# HeatBedRelay5d.net
KiCad netlist of a schematic drawn in EAGLE
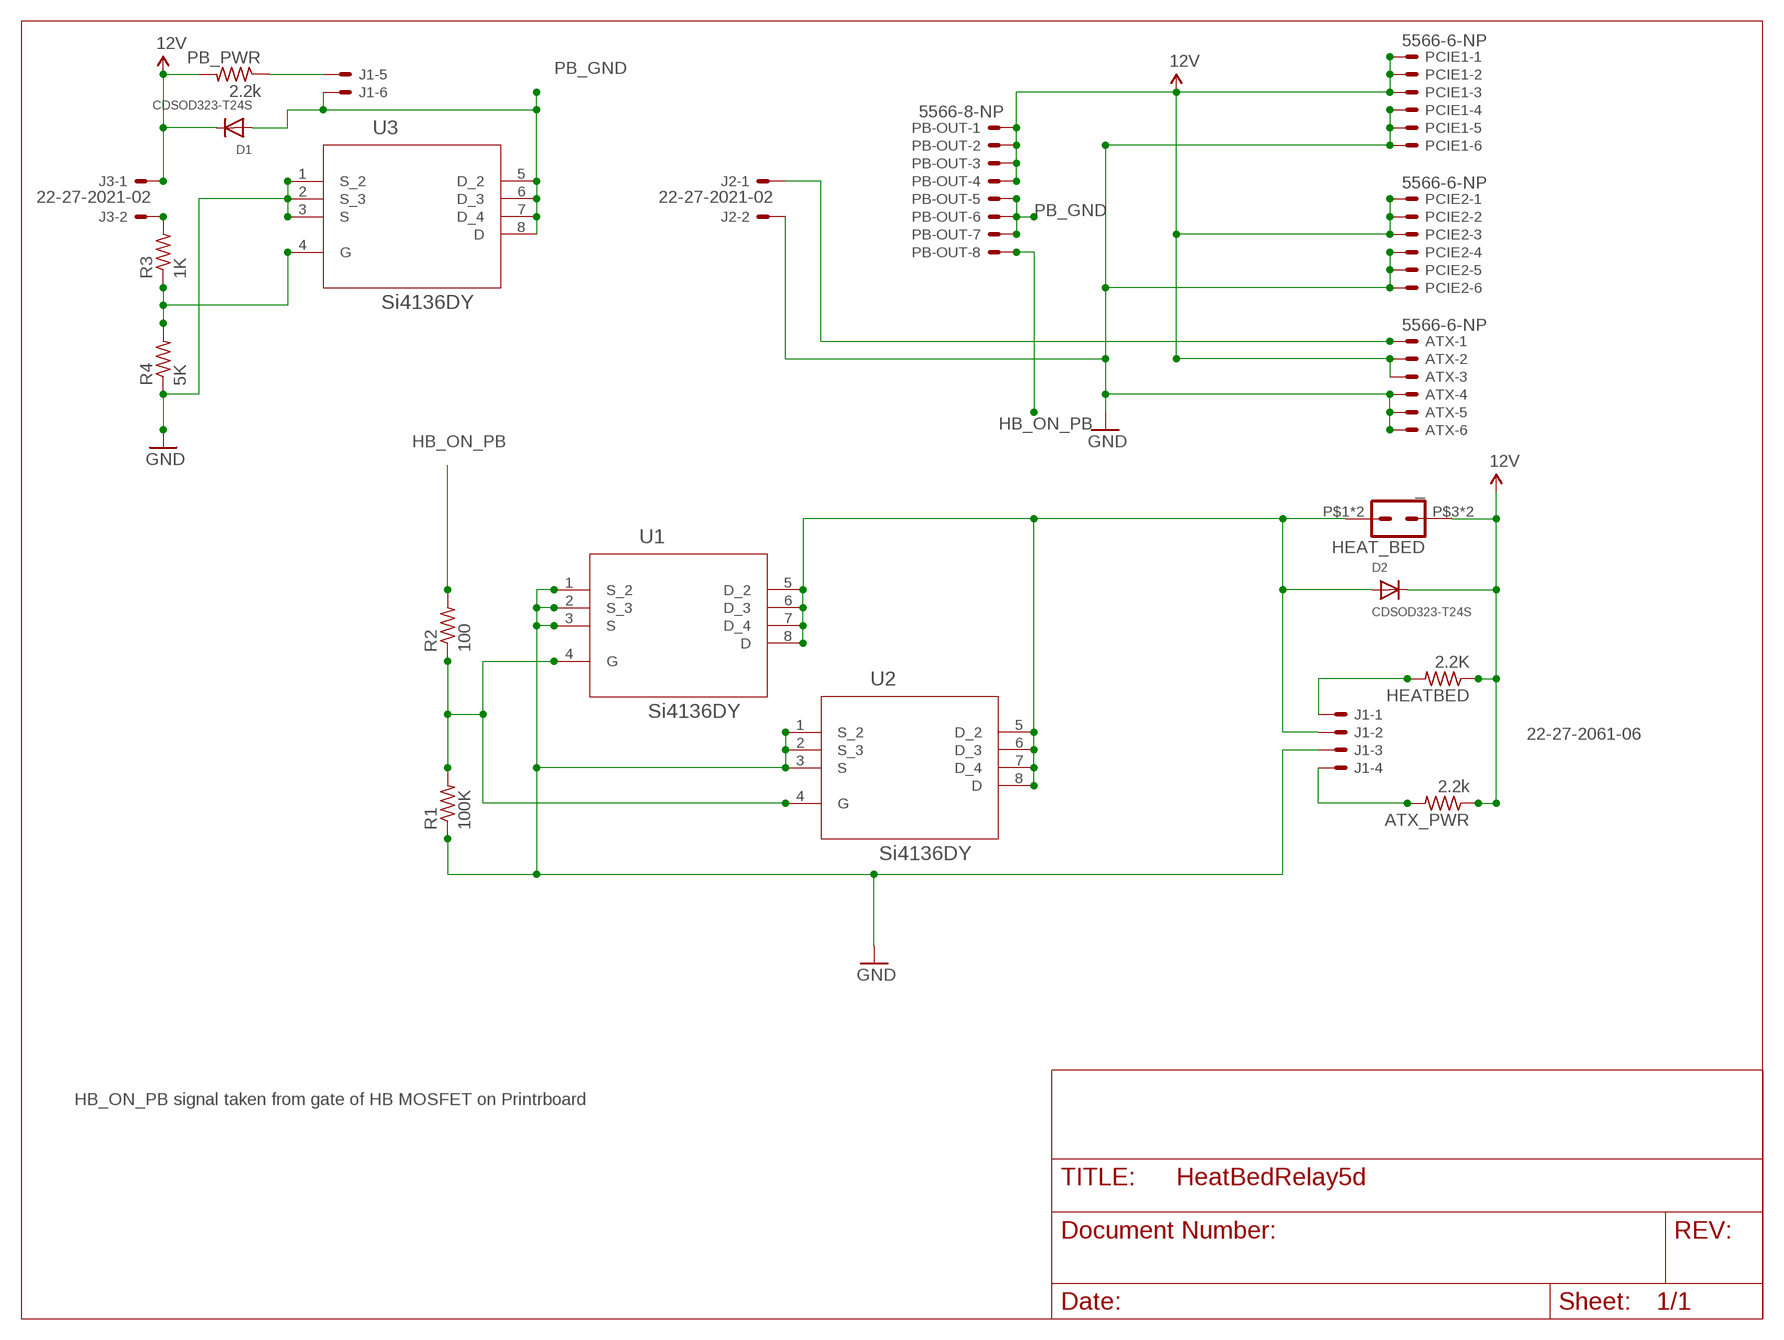
[diagram p0: schematic, sheet 1]

(export (version "E")
  (design (tool "Eeschema 10.0.6"))
  (components
    (comp (ref "ATX")
      (value "5566-6-NP")
      (footprint "eagle-import:5566-6-NP")
      (libsource (lib "eagle-import") (part "5566-6-NP"))
    )
    (comp (ref "ATX_PWR")
      (value "2.2k")
      (footprint "eagle-import:M1206")
      (libsource (lib "eagle-import") (part "R-US_M1206"))
    )
    (comp (ref "D1")
      (value "CDSOD323-T24S")
      (footprint "eagle-import:SOD-323F")
      (libsource (lib "eagle-import") (part "DIODESOD-323F"))
    )
    (comp (ref "D2")
      (value "CDSOD323-T24S")
      (footprint "eagle-import:SOD-323F")
      (libsource (lib "eagle-import") (part "DIODESOD-323F"))
    )
    (comp (ref "HEATBED")
      (value "2.2K")
      (footprint "eagle-import:M1206")
      (libsource (lib "eagle-import") (part "R-US_M1206"))
    )
    (comp (ref "HEAT_BED")
      (value "_")
      (footprint "eagle-import:MOLEX_42820-2212")
      (libsource (lib "eagle-import") (part "MOLEX_42820-2212"))
    )
    (comp (ref "J1")
      (value "22-27-2061-06")
      (footprint "eagle-import:6410-06")
      (libsource (lib "eagle-import") (part "22-?-0627-2061"))
    )
    (comp (ref "J2")
      (value "22-27-2021-02")
      (footprint "eagle-import:6410-02")
      (libsource (lib "eagle-import") (part "22-?-0227-2021"))
    )
    (comp (ref "J3")
      (value "22-27-2021-02")
      (footprint "eagle-import:6410-02")
      (libsource (lib "eagle-import") (part "22-?-0227-2021"))
    )
    (comp (ref "PB-OUT")
      (value "5566-8-NP")
      (footprint "eagle-import:5566-8-NP")
      (libsource (lib "eagle-import") (part "5566-8-NP"))
    )
    (comp (ref "PB_PWR")
      (value "2.2k")
      (footprint "eagle-import:M1206")
      (libsource (lib "eagle-import") (part "R-US_M1206"))
    )
    (comp (ref "PCIE1")
      (value "5566-6-NP")
      (footprint "eagle-import:5566-6-NP")
      (libsource (lib "eagle-import") (part "5566-6-NP"))
    )
    (comp (ref "PCIE2")
      (value "5566-6-NP")
      (footprint "eagle-import:5566-6-NP")
      (libsource (lib "eagle-import") (part "5566-6-NP"))
    )
    (comp (ref "R1")
      (value "100K")
      (footprint "eagle-import:M1206")
      (libsource (lib "eagle-import") (part "R-US_M1206"))
    )
    (comp (ref "R2")
      (value "100")
      (footprint "eagle-import:M1206")
      (libsource (lib "eagle-import") (part "R-US_M1206"))
    )
    (comp (ref "R3")
      (value "1K")
      (footprint "eagle-import:M1206")
      (libsource (lib "eagle-import") (part "R-US_M1206"))
    )
    (comp (ref "R4")
      (value "5K")
      (footprint "eagle-import:M1206")
      (libsource (lib "eagle-import") (part "R-US_M1206"))
    )
    (comp (ref "U1")
      (value "Si4136DY")
      (footprint "eagle-import:SOIC127P600X175-8N")
      (fields (field (name "MPN") "IRL6342PBF"))
      (libsource (lib "eagle-import") (part "IRL6342PBF"))
    )
    (comp (ref "U2")
      (value "Si4136DY")
      (footprint "eagle-import:SOIC127P600X175-8N")
      (fields (field (name "MPN") "IRL6342PBF"))
      (libsource (lib "eagle-import") (part "IRL6342PBF"))
    )
    (comp (ref "U3")
      (value "Si4136DY")
      (footprint "eagle-import:SOIC127P600X175-8N")
      (fields (field (name "MPN") "IRL6342PBF"))
      (libsource (lib "eagle-import") (part "IRL6342PBF"))
    )
  )
  (nets
    (net (code "1") (name "/HB_ON_PB") (class "Default")
      (node (ref "PB-OUT") (pin "8") (pinfunction "S_8") (pintype "passive"))
      (node (ref "R2") (pin "2") (pinfunction "2_2") (pintype "passive"))
    )
    (net (code "2") (name "/PB_GND") (class "Default")
      (node (ref "D1") (pin "A") (pinfunction "A_A") (pintype "passive"))
      (node (ref "J1") (pin "6") (pinfunction "S_6") (pintype "passive"))
      (node (ref "PB-OUT") (pin "5") (pinfunction "S_5") (pintype "passive"))
      (node (ref "PB-OUT") (pin "6") (pinfunction "S_6") (pintype "passive"))
      (node (ref "PB-OUT") (pin "7") (pinfunction "S_7") (pintype "passive"))
      (node (ref "U3") (pin "5") (pinfunction "D_2_5") (pintype "passive"))
      (node (ref "U3") (pin "6") (pinfunction "D_3_6") (pintype "passive"))
      (node (ref "U3") (pin "7") (pinfunction "D_4_7") (pintype "passive"))
      (node (ref "U3") (pin "8") (pinfunction "D_8") (pintype "passive"))
    )
    (net (code "3") (name "12V") (class "Default")
      (node (ref "ATX") (pin "2") (pinfunction "S_2") (pintype "passive"))
      (node (ref "ATX") (pin "3") (pinfunction "S_3") (pintype "passive"))
      (node (ref "ATX_PWR") (pin "1") (pinfunction "1_1") (pintype "passive"))
      (node (ref "D1") (pin "C") (pinfunction "C_C") (pintype "passive"))
      (node (ref "D2") (pin "C") (pinfunction "C_C") (pintype "passive"))
      (node (ref "HEATBED") (pin "1") (pinfunction "1_1") (pintype "passive"))
      (node (ref "HEAT_BED") (pin "P$3") (pinfunction "1_P$3") (pintype "passive"))
      (node (ref "HEAT_BED") (pin "P$4") (pinfunction "1_P$4") (pintype "passive"))
      (node (ref "J3") (pin "1") (pinfunction "S_1") (pintype "passive"))
      (node (ref "PB-OUT") (pin "1") (pinfunction "S_1") (pintype "passive"))
      (node (ref "PB-OUT") (pin "2") (pinfunction "S_2") (pintype "passive"))
      (node (ref "PB-OUT") (pin "3") (pinfunction "S_3") (pintype "passive"))
      (node (ref "PB-OUT") (pin "4") (pinfunction "S_4") (pintype "passive"))
      (node (ref "PB_PWR") (pin "2") (pinfunction "2_2") (pintype "passive"))
      (node (ref "PCIE1") (pin "1") (pinfunction "S_1") (pintype "passive"))
      (node (ref "PCIE1") (pin "2") (pinfunction "S_2") (pintype "passive"))
      (node (ref "PCIE1") (pin "3") (pinfunction "S_3") (pintype "passive"))
      (node (ref "PCIE2") (pin "1") (pinfunction "S_1") (pintype "passive"))
      (node (ref "PCIE2") (pin "2") (pinfunction "S_2") (pintype "passive"))
      (node (ref "PCIE2") (pin "3") (pinfunction "S_3") (pintype "passive"))
    )
    (net (code "4") (name "GND") (class "Default")
      (node (ref "ATX") (pin "4") (pinfunction "S_4") (pintype "passive"))
      (node (ref "ATX") (pin "5") (pinfunction "S_5") (pintype "passive"))
      (node (ref "ATX") (pin "6") (pinfunction "S_6") (pintype "passive"))
      (node (ref "J1") (pin "3") (pinfunction "S_3") (pintype "passive"))
      (node (ref "J2") (pin "2") (pinfunction "S_2") (pintype "passive"))
      (node (ref "PCIE1") (pin "4") (pinfunction "S_4") (pintype "passive"))
      (node (ref "PCIE1") (pin "5") (pinfunction "S_5") (pintype "passive"))
      (node (ref "PCIE1") (pin "6") (pinfunction "S_6") (pintype "passive"))
      (node (ref "PCIE2") (pin "4") (pinfunction "S_4") (pintype "passive"))
      (node (ref "PCIE2") (pin "5") (pinfunction "S_5") (pintype "passive"))
      (node (ref "PCIE2") (pin "6") (pinfunction "S_6") (pintype "passive"))
      (node (ref "R1") (pin "1") (pinfunction "1_1") (pintype "passive"))
      (node (ref "R4") (pin "1") (pinfunction "1_1") (pintype "passive"))
      (node (ref "U1") (pin "1") (pinfunction "S_2_1") (pintype "passive"))
      (node (ref "U1") (pin "2") (pinfunction "S_3_2") (pintype "passive"))
      (node (ref "U1") (pin "3") (pinfunction "S_3") (pintype "passive"))
      (node (ref "U2") (pin "1") (pinfunction "S_2_1") (pintype "passive"))
      (node (ref "U2") (pin "2") (pinfunction "S_3_2") (pintype "passive"))
      (node (ref "U2") (pin "3") (pinfunction "S_3") (pintype "passive"))
      (node (ref "U3") (pin "1") (pinfunction "S_2_1") (pintype "passive"))
      (node (ref "U3") (pin "2") (pinfunction "S_3_2") (pintype "passive"))
      (node (ref "U3") (pin "3") (pinfunction "S_3") (pintype "passive"))
    )
    (net (code "5") (name "Net-(ATXA-S)") (class "Default")
      (node (ref "ATX") (pin "1") (pinfunction "S_1") (pintype "passive"))
      (node (ref "J2") (pin "1") (pinfunction "S_1") (pintype "passive"))
    )
    (net (code "6") (name "Net-(J1A-S)") (class "Default")
      (node (ref "HEATBED") (pin "2") (pinfunction "2_2") (pintype "passive"))
      (node (ref "J1") (pin "1") (pinfunction "S_1") (pintype "passive"))
    )
    (net (code "7") (name "Net-(J1B-S)") (class "Default")
      (node (ref "D2") (pin "A") (pinfunction "A_A") (pintype "passive"))
      (node (ref "HEAT_BED") (pin "P$1") (pinfunction "2_P$1") (pintype "passive"))
      (node (ref "HEAT_BED") (pin "P$2") (pinfunction "2_P$2") (pintype "passive"))
      (node (ref "J1") (pin "2") (pinfunction "S_2") (pintype "passive"))
      (node (ref "U1") (pin "5") (pinfunction "D_2_5") (pintype "passive"))
      (node (ref "U1") (pin "6") (pinfunction "D_3_6") (pintype "passive"))
      (node (ref "U1") (pin "7") (pinfunction "D_4_7") (pintype "passive"))
      (node (ref "U1") (pin "8") (pinfunction "D_8") (pintype "passive"))
      (node (ref "U2") (pin "5") (pinfunction "D_2_5") (pintype "passive"))
      (node (ref "U2") (pin "6") (pinfunction "D_3_6") (pintype "passive"))
      (node (ref "U2") (pin "7") (pinfunction "D_4_7") (pintype "passive"))
      (node (ref "U2") (pin "8") (pinfunction "D_8") (pintype "passive"))
    )
    (net (code "8") (name "Net-(J1D-S)") (class "Default")
      (node (ref "ATX_PWR") (pin "2") (pinfunction "2_2") (pintype "passive"))
      (node (ref "J1") (pin "4") (pinfunction "S_4") (pintype "passive"))
    )
    (net (code "9") (name "Net-(J1E-S)") (class "Default")
      (node (ref "J1") (pin "5") (pinfunction "S_5") (pintype "passive"))
      (node (ref "PB_PWR") (pin "1") (pinfunction "1_1") (pintype "passive"))
    )
    (net (code "10") (name "Net-(J3B-S)") (class "Default")
      (node (ref "J3") (pin "2") (pinfunction "S_2") (pintype "passive"))
      (node (ref "R3") (pin "2") (pinfunction "2_2") (pintype "passive"))
    )
    (net (code "11") (name "Net-(U1-G)") (class "Default")
      (node (ref "R1") (pin "2") (pinfunction "2_2") (pintype "passive"))
      (node (ref "R2") (pin "1") (pinfunction "1_1") (pintype "passive"))
      (node (ref "U1") (pin "4") (pinfunction "G_4") (pintype "passive"))
      (node (ref "U2") (pin "4") (pinfunction "G_4") (pintype "passive"))
    )
    (net (code "12") (name "Net-(U3-G)") (class "Default")
      (node (ref "R3") (pin "1") (pinfunction "1_1") (pintype "passive"))
      (node (ref "R4") (pin "2") (pinfunction "2_2") (pintype "passive"))
      (node (ref "U3") (pin "4") (pinfunction "G_4") (pintype "passive"))
    )
  )
)
